# v1_0.net
KiCad netlist of a schematic drawn in Altium Designer
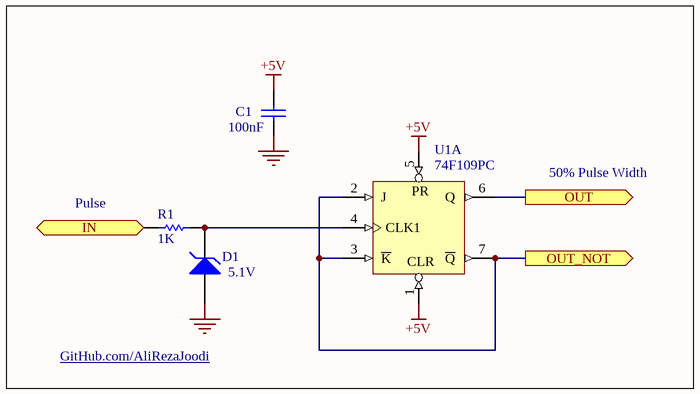
[diagram p0: v1.0.SchDoc]

(export (version "E")
  (design (tool "Eeschema 10.0.6"))
  (components
    (comp (ref "C1")
      (value "100nF")
      (footprint "CAPNTO2.54-3.05x1.78A")
      (description "Capacitor")
      (fields (field (name "MANUFACTURER") "Generic Components") (field (name "PUBLISHER") "Altium Limited"))
      (libsource (lib "Miscellaneous Devices") (part "Cap"))
    )
    (comp (ref "D1")
      (value "5.1V")
      (footprint "DIODE0.4_Glass")
      (description "Zener Diode")
      (fields (field (name "MANUFACTURER") "Generic Components") (field (name "PUBLISHER") "Altium Limited"))
      (libsource (lib "Miscellaneous Devices") (part "D Zener"))
    )
    (comp (ref "R1")
      (value "1K")
      (footprint "AXIAL-0.4")
      (description "Resistor")
      (fields (field (name "PUBLISHER") "Altium Limited"))
      (libsource (lib "Miscellaneous Devices") (part "Res1"))
    )
    (comp (ref "U1")
      (value "74F109PC")
      (footprint "N16E")
      (description "Dual J-K Positive Edge-Triggered Flip-Flop")
      (fields (field (name "PUBLISHER") "Altium Limited"))
      (libsource (lib "FSC Logic Flip-Flop") (part "74F109PC"))
    )
  )
  (nets
    (net (code "1") (name "+5V") (class "Default")
      (node (ref "C1") (pin "2") (pinfunction "2_2") (pintype "passive"))
      (node (ref "U1") (pin "1") (pinfunction "CLR_1") (pintype "input"))
      (node (ref "U1") (pin "5") (pinfunction "PR_5") (pintype "input"))
    )
    (net (code "2") (name "/IN") (class "Default")
      (node (ref "R1") (pin "2") (pinfunction "2_2") (pintype "passive"))
    )
    (net (code "3") (name "/OUT") (class "Default")
      (node (ref "U1") (pin "6") (pinfunction "Q_6") (pintype "output"))
    )
    (net (code "4") (name "/OUT_NOT") (class "Default")
      (node (ref "U1") (pin "2") (pinfunction "J_2") (pintype "input"))
      (node (ref "U1") (pin "3") (pinfunction "~{K}_3") (pintype "input"))
      (node (ref "U1") (pin "7") (pinfunction "~{Q}_7") (pintype "output"))
    )
    (net (code "5") (name "GND") (class "Default")
      (node (ref "C1") (pin "1") (pinfunction "1_1") (pintype "passive"))
      (node (ref "D1") (pin "1") (pinfunction "A_1") (pintype "passive"))
      (node (ref "U1") (pin "8") (pinfunction "GND_8") (pintype "power_in"))
    )
    (net (code "6") (name "Net-(D1-K)") (class "Default")
      (node (ref "D1") (pin "2") (pinfunction "K_2") (pintype "passive"))
      (node (ref "R1") (pin "1") (pinfunction "1_1") (pintype "passive"))
      (node (ref "U1") (pin "4") (pinfunction "CLK1_4") (pintype "input"))
    )
    (net (code "7") (name "VCC") (class "Default")
      (node (ref "U1") (pin "16") (pinfunction "VCC_16") (pintype "power_in"))
    )
  )
)
